# KeyBoard.net
KiCad netlist of a schematic drawn in Altium Designer
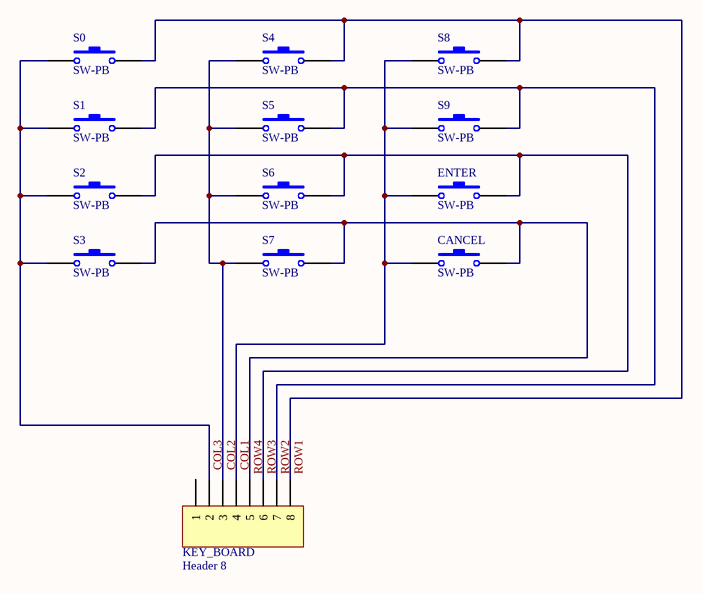
[diagram p0: KeyBoard.SchDoc]

(export (version "E")
  (design (tool "Eeschema 10.0.6"))
  (components
    (comp (ref "CANCEL")
      (value "SW-PB")
      (footprint "Device:BUTTON")
      (description "Switch")
      (fields (field (name "PUBLISHER") "Altium Limited"))
      (libsource (lib "Miscellaneous Devices") (part "SW-PB"))
    )
    (comp (ref "ENTER")
      (value "SW-PB")
      (footprint "Device:BUTTON")
      (description "Switch")
      (fields (field (name "PUBLISHER") "Altium Limited"))
      (libsource (lib "Miscellaneous Devices") (part "SW-PB"))
    )
    (comp (ref "KEY_BOARD")
      (value "Header 8")
      (footprint "Device:Cap_8")
      (description "Header, 8-Pin")
      (fields (field (name "PUBLISHER") "Altium Limited"))
      (libsource (lib "Miscellaneous Connectors") (part "Header 8"))
    )
    (comp (ref "S0")
      (value "SW-PB")
      (footprint "Device:BUTTON")
      (description "Switch")
      (fields (field (name "PUBLISHER") "Altium Limited"))
      (libsource (lib "Miscellaneous Devices") (part "SW-PB"))
    )
    (comp (ref "S1")
      (value "SW-PB")
      (footprint "Device:BUTTON")
      (description "Switch")
      (fields (field (name "PUBLISHER") "Altium Limited"))
      (libsource (lib "Miscellaneous Devices") (part "SW-PB"))
    )
    (comp (ref "S2")
      (value "SW-PB")
      (footprint "Device:BUTTON")
      (description "Switch")
      (fields (field (name "PUBLISHER") "Altium Limited"))
      (libsource (lib "Miscellaneous Devices") (part "SW-PB"))
    )
    (comp (ref "S3")
      (value "SW-PB")
      (footprint "Device:BUTTON")
      (description "Switch")
      (fields (field (name "PUBLISHER") "Altium Limited"))
      (libsource (lib "Miscellaneous Devices") (part "SW-PB"))
    )
    (comp (ref "S4")
      (value "SW-PB")
      (footprint "Device:BUTTON")
      (description "Switch")
      (fields (field (name "PUBLISHER") "Altium Limited"))
      (libsource (lib "Miscellaneous Devices") (part "SW-PB"))
    )
    (comp (ref "S5")
      (value "SW-PB")
      (footprint "Device:BUTTON")
      (description "Switch")
      (fields (field (name "PUBLISHER") "Altium Limited"))
      (libsource (lib "Miscellaneous Devices") (part "SW-PB"))
    )
    (comp (ref "S6")
      (value "SW-PB")
      (footprint "Device:BUTTON")
      (description "Switch")
      (fields (field (name "PUBLISHER") "Altium Limited"))
      (libsource (lib "Miscellaneous Devices") (part "SW-PB"))
    )
    (comp (ref "S7")
      (value "SW-PB")
      (footprint "Device:BUTTON")
      (description "Switch")
      (fields (field (name "PUBLISHER") "Altium Limited"))
      (libsource (lib "Miscellaneous Devices") (part "SW-PB"))
    )
    (comp (ref "S8")
      (value "SW-PB")
      (footprint "Device:BUTTON")
      (description "Switch")
      (fields (field (name "PUBLISHER") "Altium Limited"))
      (libsource (lib "Miscellaneous Devices") (part "SW-PB"))
    )
    (comp (ref "S9")
      (value "SW-PB")
      (footprint "Device:BUTTON")
      (description "Switch")
      (fields (field (name "PUBLISHER") "Altium Limited"))
      (libsource (lib "Miscellaneous Devices") (part "SW-PB"))
    )
  )
  (nets
    (net (code "1") (name "/COL1") (class "Default")
      (node (ref "CANCEL") (pin "1") (pinfunction "1_1") (pintype "passive"))
      (node (ref "ENTER") (pin "1") (pinfunction "1_1") (pintype "passive"))
      (node (ref "KEY_BOARD") (pin "4") (pinfunction "4_4") (pintype "passive"))
      (node (ref "S8") (pin "1") (pinfunction "1_1") (pintype "passive"))
      (node (ref "S9") (pin "1") (pinfunction "1_1") (pintype "passive"))
    )
    (net (code "2") (name "/COL2") (class "Default")
      (node (ref "KEY_BOARD") (pin "3") (pinfunction "3_3") (pintype "passive"))
      (node (ref "S4") (pin "1") (pinfunction "1_1") (pintype "passive"))
      (node (ref "S5") (pin "1") (pinfunction "1_1") (pintype "passive"))
      (node (ref "S6") (pin "1") (pinfunction "1_1") (pintype "passive"))
      (node (ref "S7") (pin "1") (pinfunction "1_1") (pintype "passive"))
    )
    (net (code "3") (name "/COL3") (class "Default")
      (node (ref "KEY_BOARD") (pin "2") (pinfunction "2_2") (pintype "passive"))
      (node (ref "S0") (pin "1") (pinfunction "1_1") (pintype "passive"))
      (node (ref "S1") (pin "1") (pinfunction "1_1") (pintype "passive"))
      (node (ref "S2") (pin "1") (pinfunction "1_1") (pintype "passive"))
      (node (ref "S3") (pin "1") (pinfunction "1_1") (pintype "passive"))
    )
    (net (code "4") (name "/ROW1") (class "Default")
      (node (ref "KEY_BOARD") (pin "8") (pinfunction "8_8") (pintype "passive"))
      (node (ref "S0") (pin "2") (pinfunction "2_2") (pintype "passive"))
      (node (ref "S4") (pin "2") (pinfunction "2_2") (pintype "passive"))
      (node (ref "S8") (pin "2") (pinfunction "2_2") (pintype "passive"))
    )
    (net (code "5") (name "/ROW2") (class "Default")
      (node (ref "KEY_BOARD") (pin "7") (pinfunction "7_7") (pintype "passive"))
      (node (ref "S1") (pin "2") (pinfunction "2_2") (pintype "passive"))
      (node (ref "S5") (pin "2") (pinfunction "2_2") (pintype "passive"))
      (node (ref "S9") (pin "2") (pinfunction "2_2") (pintype "passive"))
    )
    (net (code "6") (name "/ROW3") (class "Default")
      (node (ref "ENTER") (pin "2") (pinfunction "2_2") (pintype "passive"))
      (node (ref "KEY_BOARD") (pin "6") (pinfunction "6_6") (pintype "passive"))
      (node (ref "S2") (pin "2") (pinfunction "2_2") (pintype "passive"))
      (node (ref "S6") (pin "2") (pinfunction "2_2") (pintype "passive"))
    )
    (net (code "7") (name "/ROW4") (class "Default")
      (node (ref "CANCEL") (pin "2") (pinfunction "2_2") (pintype "passive"))
      (node (ref "KEY_BOARD") (pin "5") (pinfunction "5_5") (pintype "passive"))
      (node (ref "S3") (pin "2") (pinfunction "2_2") (pintype "passive"))
      (node (ref "S7") (pin "2") (pinfunction "2_2") (pintype "passive"))
    )
    (net (code "8") (name "unconnected-(KEY_BOARD-Pad1)") (class "Default")
      (node (ref "KEY_BOARD") (pin "1") (pinfunction "1_1") (pintype "passive"))
    )
  )
)
